# NES_IO.net
KiCad netlist of a schematic drawn in EAGLE
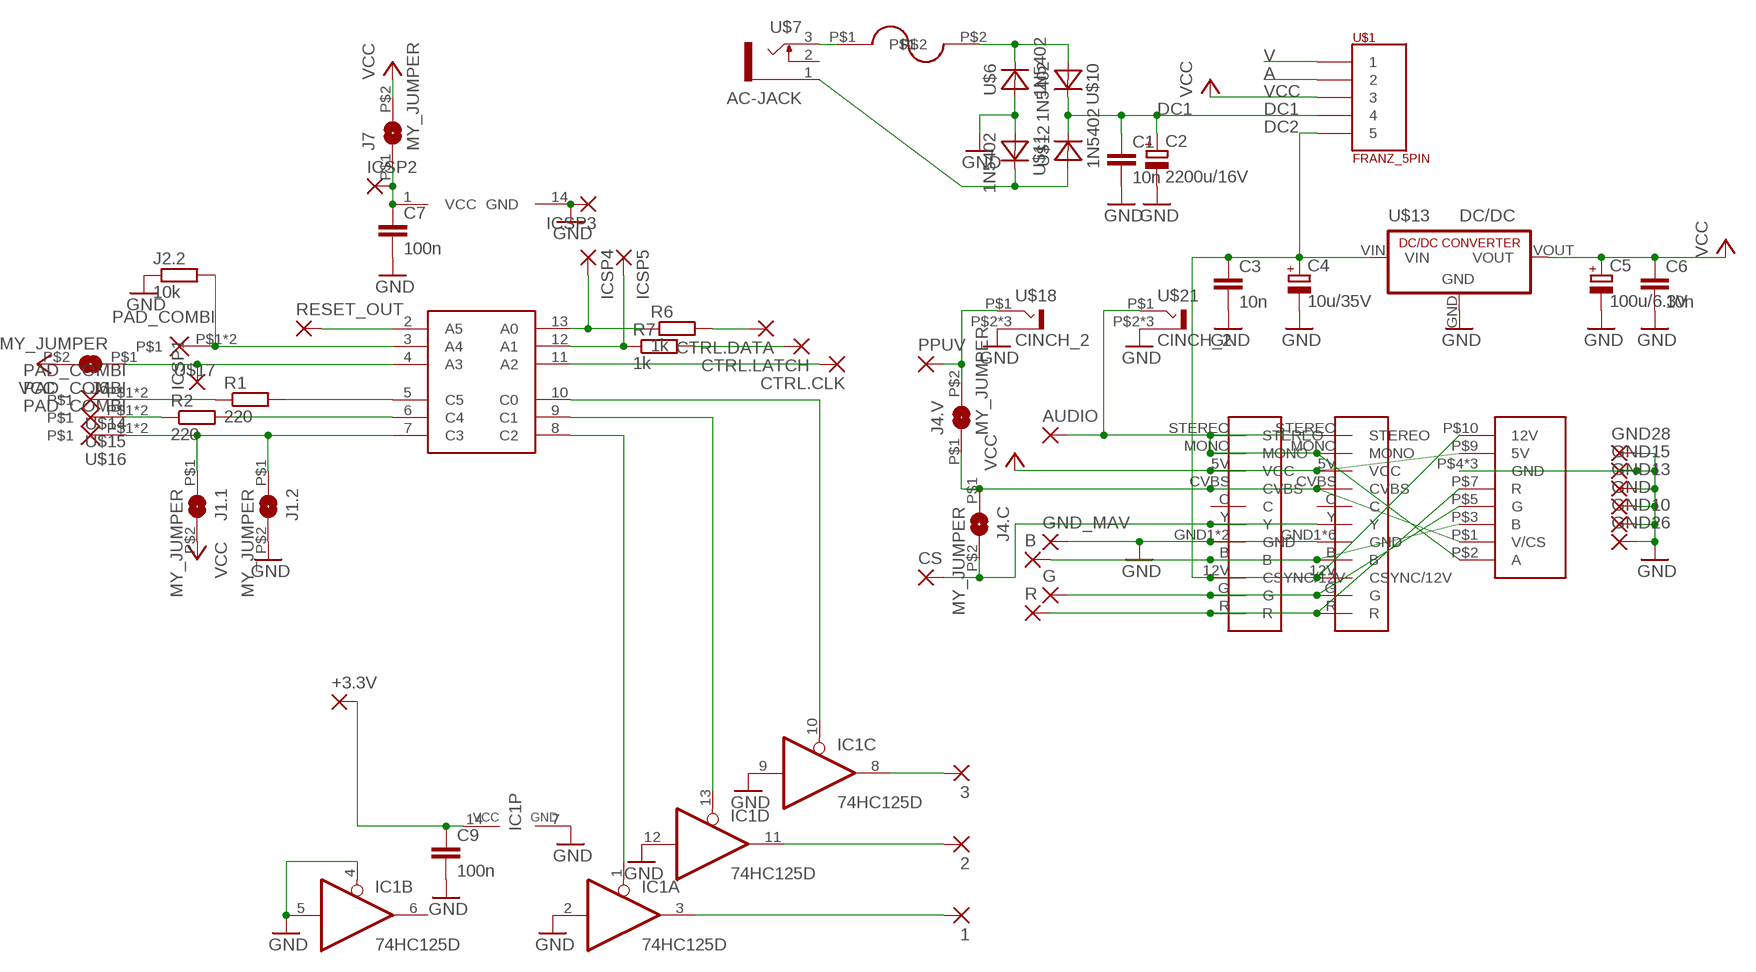
[diagram p0: schematic, sheet 1]

(export (version "E")
  (design (tool "Eeschema 10.0.6"))
  (components
    (comp (ref "+3.3V")
      (value "SMD2")
      (footprint "eagle-import:SMD1,27-2,54")
      (libsource (lib "eagle-import") (part "SMD2"))
    )
    (comp (ref "1")
      (value "SMD2")
      (footprint "eagle-import:SMD1,27-2,54")
      (libsource (lib "eagle-import") (part "SMD2"))
    )
    (comp (ref "2")
      (value "SMD2")
      (footprint "eagle-import:SMD1,27-2,54")
      (libsource (lib "eagle-import") (part "SMD2"))
    )
    (comp (ref "3")
      (value "SMD2")
      (footprint "eagle-import:SMD1,27-2,54")
      (libsource (lib "eagle-import") (part "SMD2"))
    )
    (comp (ref "AUDIO")
      (value "SMD2")
      (footprint "eagle-import:SMD1,27-2,54")
      (libsource (lib "eagle-import") (part "SMD2"))
    )
    (comp (ref "B")
      (value "SMD2")
      (footprint "eagle-import:SMD1,27-2,54")
      (libsource (lib "eagle-import") (part "SMD2"))
    )
    (comp (ref "C1")
      (value "10n")
      (footprint "eagle-import:Z0805")
      (libsource (lib "eagle-import") (part "C0805"))
    )
    (comp (ref "C2")
      (value "2200u/16V")
      (footprint "eagle-import:E5-13")
      (libsource (lib "eagle-import") (part "resistor_CPOL-EUE5-13"))
    )
    (comp (ref "C3")
      (value "10n")
      (footprint "eagle-import:Z0805")
      (libsource (lib "eagle-import") (part "C0805"))
    )
    (comp (ref "C4")
      (value "10u/35V")
      (footprint "eagle-import:PANASONIC_B")
      (libsource (lib "eagle-import") (part "CPOL-EUB"))
    )
    (comp (ref "C5")
      (value "100u/6.3V")
      (footprint "eagle-import:PANASONIC_D")
      (libsource (lib "eagle-import") (part "CPOL-EUD"))
    )
    (comp (ref "C6")
      (value "10n")
      (footprint "eagle-import:Z0805")
      (libsource (lib "eagle-import") (part "C0805"))
    )
    (comp (ref "C7")
      (value "100n")
      (footprint "eagle-import:Z0805")
      (libsource (lib "eagle-import") (part "C0805"))
    )
    (comp (ref "C9")
      (value "100n")
      (footprint "eagle-import:Z0805")
      (libsource (lib "eagle-import") (part "C0805"))
    )
    (comp (ref "CS")
      (value "SMD2")
      (footprint "eagle-import:SMD1,27-2,54")
      (libsource (lib "eagle-import") (part "SMD2"))
    )
    (comp (ref "CTRL.CLK")
      (value "SMD2")
      (footprint "eagle-import:SMD1,27-2,54")
      (libsource (lib "eagle-import") (part "SMD2"))
    )
    (comp (ref "CTRL.DATA")
      (value "SMD2")
      (footprint "eagle-import:SMD1,27-2,54")
      (libsource (lib "eagle-import") (part "SMD2"))
    )
    (comp (ref "CTRL.LATCH")
      (value "SMD2")
      (footprint "eagle-import:SMD1,27-2,54")
      (libsource (lib "eagle-import") (part "SMD2"))
    )
    (comp (ref "G")
      (value "SMD2")
      (footprint "eagle-import:SMD1,27-2,54")
      (libsource (lib "eagle-import") (part "SMD2"))
    )
    (comp (ref "GND")
      (value "SMD5")
      (footprint "eagle-import:SMD2,54-5,08")
      (libsource (lib "eagle-import") (part "SMD5"))
    )
    (comp (ref "GND10")
      (value "SMD5")
      (footprint "eagle-import:SMD2,54-5,08")
      (libsource (lib "eagle-import") (part "SMD5"))
    )
    (comp (ref "GND13")
      (value "SMD5")
      (footprint "eagle-import:SMD2,54-5,08")
      (libsource (lib "eagle-import") (part "SMD5"))
    )
    (comp (ref "GND15")
      (value "SMD5")
      (footprint "eagle-import:SMD2,54-5,08")
      (libsource (lib "eagle-import") (part "SMD5"))
    )
    (comp (ref "GND26")
      (value "SMD5")
      (footprint "eagle-import:SMD2,54-5,08")
      (libsource (lib "eagle-import") (part "SMD5"))
    )
    (comp (ref "GND28")
      (value "SMD5")
      (footprint "eagle-import:SMD2,54-5,08")
      (libsource (lib "eagle-import") (part "SMD5"))
    )
    (comp (ref "GND_MAV")
      (value "SMD2")
      (footprint "eagle-import:SMD1,27-2,54")
      (libsource (lib "eagle-import") (part "SMD2"))
    )
    (comp (ref "IC1")
      (value "74HC125D")
      (footprint "eagle-import:SO14")
      (libsource (lib "eagle-import") (part "74125DHC"))
    )
    (comp (ref "ICSP1")
      (value "1,6/0,8")
      (footprint "eagle-import:1,6_0,8")
      (libsource (lib "eagle-import") (part "1,6/0,8"))
    )
    (comp (ref "ICSP2")
      (value "1,6/0,8")
      (footprint "eagle-import:1,6_0,8")
      (libsource (lib "eagle-import") (part "1,6/0,8"))
    )
    (comp (ref "ICSP3")
      (value "1,6/0,8")
      (footprint "eagle-import:1,6_0,8")
      (libsource (lib "eagle-import") (part "1,6/0,8"))
    )
    (comp (ref "ICSP4")
      (value "1,6/0,8")
      (footprint "eagle-import:1,6_0,8")
      (libsource (lib "eagle-import") (part "1,6/0,8"))
    )
    (comp (ref "ICSP5")
      (value "1,6/0,8")
      (footprint "eagle-import:1,6_0,8")
      (libsource (lib "eagle-import") (part "1,6/0,8"))
    )
    (comp (ref "J1.1")
      (value "MY_JUMPER")
      (footprint "eagle-import:MYJUMP")
      (libsource (lib "eagle-import") (part "MY_JUMPER"))
    )
    (comp (ref "J1.2")
      (value "MY_JUMPER")
      (footprint "eagle-import:MYJUMP")
      (libsource (lib "eagle-import") (part "MY_JUMPER"))
    )
    (comp (ref "J2.2")
      (value "10k")
      (footprint "eagle-import:Z0805")
      (libsource (lib "eagle-import") (part "R0805"))
    )
    (comp (ref "J4.C")
      (value "MY_JUMPER")
      (footprint "eagle-import:MYJUMP")
      (libsource (lib "eagle-import") (part "MY_JUMPER"))
    )
    (comp (ref "J4.V")
      (value "MY_JUMPER")
      (footprint "eagle-import:MYJUMP")
      (libsource (lib "eagle-import") (part "MY_JUMPER"))
    )
    (comp (ref "J6")
      (value "MY_JUMPER")
      (footprint "eagle-import:MYJUMP")
      (libsource (lib "eagle-import") (part "MY_JUMPER"))
    )
    (comp (ref "J7")
      (value "MY_JUMPER")
      (footprint "eagle-import:MYJUMP")
      (libsource (lib "eagle-import") (part "MY_JUMPER"))
    )
    (comp (ref "PPUV")
      (value "SMD2")
      (footprint "eagle-import:SMD1,27-2,54")
      (libsource (lib "eagle-import") (part "SMD2"))
    )
    (comp (ref "R")
      (value "SMD2")
      (footprint "eagle-import:SMD1,27-2,54")
      (libsource (lib "eagle-import") (part "SMD2"))
    )
    (comp (ref "R1")
      (value "220")
      (footprint "eagle-import:Z0805")
      (libsource (lib "eagle-import") (part "R0805"))
    )
    (comp (ref "R2")
      (value "220")
      (footprint "eagle-import:Z0805")
      (libsource (lib "eagle-import") (part "R0805"))
    )
    (comp (ref "R6")
      (value "1k")
      (footprint "eagle-import:Z0805")
      (libsource (lib "eagle-import") (part "R0805"))
    )
    (comp (ref "R7")
      (value "1k")
      (footprint "eagle-import:Z0805")
      (libsource (lib "eagle-import") (part "R0805"))
    )
    (comp (ref "RESET_OUT")
      (value "SMD2")
      (footprint "eagle-import:SMD1,27-2,54")
      (libsource (lib "eagle-import") (part "SMD2"))
    )
    (comp (ref "U$1")
      (value "FRANZ_5PIN")
      (footprint "eagle-import:5X2.22RM4")
      (libsource (lib "eagle-import") (part "FRANZ_5PIN"))
    )
    (comp (ref "U$2")
      (value "FUSEHOLDER")
      (footprint "eagle-import:FUSEHOLDER")
      (libsource (lib "eagle-import") (part "FUSEHOLDER"))
    )
    (comp (ref "U$5")
      (value "PIC16F630_SIMPLE")
      (footprint "eagle-import:PIC16F630")
      (libsource (lib "eagle-import") (part "PIC16F630_SIMPLE"))
    )
    (comp (ref "U$6")
      (value "1N5402")
      (footprint "eagle-import:DO201")
      (libsource (lib "eagle-import") (part "1N5402"))
    )
    (comp (ref "U$7")
      (value "AC-JACK")
      (footprint "eagle-import:AC-JACK")
      (libsource (lib "eagle-import") (part "AC-JACK"))
    )
    (comp (ref "U$8")
      (value "NESFR_JACK2")
      (footprint "eagle-import:NESFR_JACK2")
      (libsource (lib "eagle-import") (part "NESFR_JACK2"))
    )
    (comp (ref "U$10")
      (value "1N5402")
      (footprint "eagle-import:DO201")
      (libsource (lib "eagle-import") (part "1N5402"))
    )
    (comp (ref "U$11")
      (value "1N5402")
      (footprint "eagle-import:DO201")
      (libsource (lib "eagle-import") (part "1N5402"))
    )
    (comp (ref "U$12")
      (value "1N5402")
      (footprint "eagle-import:DO201")
      (libsource (lib "eagle-import") (part "1N5402"))
    )
    (comp (ref "U$13")
      (value "DC/DC")
      (footprint "eagle-import:RECOM")
      (libsource (lib "eagle-import") (part "DC/DC"))
    )
    (comp (ref "U$14")
      (value "PAD_COMBI")
      (footprint "eagle-import:PAD_COMBI")
      (libsource (lib "eagle-import") (part "PAD_COMBI"))
    )
    (comp (ref "U$15")
      (value "PAD_COMBI")
      (footprint "eagle-import:PAD_COMBI")
      (libsource (lib "eagle-import") (part "PAD_COMBI"))
    )
    (comp (ref "U$16")
      (value "PAD_COMBI")
      (footprint "eagle-import:PAD_COMBI")
      (libsource (lib "eagle-import") (part "PAD_COMBI"))
    )
    (comp (ref "U$17")
      (value "PAD_COMBI")
      (footprint "eagle-import:PAD_COMBI")
      (libsource (lib "eagle-import") (part "PAD_COMBI"))
    )
    (comp (ref "U$18")
      (value "CINCH_2")
      (footprint "eagle-import:CINCH_2")
      (libsource (lib "eagle-import") (part "CINCH_2"))
    )
    (comp (ref "U$19")
      (value "GC-MULTIAV")
      (footprint "eagle-import:GC-MULTIAV")
      (libsource (lib "eagle-import") (part "GC-MULTIAV"))
    )
    (comp (ref "U$20")
      (value "SNES-MULTIAV2")
      (footprint "eagle-import:SNES-MULTIAV2")
      (libsource (lib "eagle-import") (part "SNES-MULTIAV2"))
    )
    (comp (ref "U$21")
      (value "CINCH_2")
      (footprint "eagle-import:CINCH_2")
      (libsource (lib "eagle-import") (part "CINCH_2"))
    )
  )
  (nets
    (net (code "1") (name "/A") (class "Default")
      (node (ref "U$1") (pin "P$2") (pinfunction "2_P$2") (pintype "bidirectional"))
    )
    (net (code "2") (name "/DC1") (class "Default")
      (node (ref "C1") (pin "1") (pinfunction "1_1") (pintype "passive"))
      (node (ref "C2") (pin "+") (pinfunction "+_+") (pintype "passive"))
      (node (ref "U$1") (pin "P$4") (pinfunction "4_P$4") (pintype "bidirectional"))
      (node (ref "U$10") (pin "C") (pinfunction "C_C") (pintype "passive"))
      (node (ref "U$12") (pin "C") (pinfunction "C_C") (pintype "passive"))
    )
    (net (code "3") (name "/DC2") (class "Default")
      (node (ref "C3") (pin "1") (pinfunction "1_1") (pintype "passive"))
      (node (ref "C4") (pin "+") (pinfunction "+_+") (pintype "passive"))
      (node (ref "U$1") (pin "P$5") (pinfunction "5_P$5") (pintype "bidirectional"))
      (node (ref "U$13") (pin "VIN") (pinfunction "VIN_VIN") (pintype "passive"))
      (node (ref "U$19") (pin "12V") (pinfunction "CSYNC/12V_12V") (pintype "output"))
      (node (ref "U$20") (pin "12V") (pinfunction "CSYNC/12V_12V") (pintype "output"))
      (node (ref "U$8") (pin "P$10") (pinfunction "12V_P$10") (pintype "bidirectional"))
    )
    (net (code "4") (name "/V") (class "Default")
      (node (ref "U$1") (pin "P$1") (pinfunction "1_P$1") (pintype "bidirectional"))
    )
    (net (code "5") (name "GND") (class "Default")
      (node (ref "C1") (pin "2") (pinfunction "2_2") (pintype "passive"))
      (node (ref "C2") (pin "-") (pinfunction "-_-") (pintype "passive"))
      (node (ref "C3") (pin "2") (pinfunction "2_2") (pintype "passive"))
      (node (ref "C4") (pin "-") (pinfunction "-_-") (pintype "passive"))
      (node (ref "C5") (pin "-") (pinfunction "-_-") (pintype "passive"))
      (node (ref "C6") (pin "2") (pinfunction "2_2") (pintype "passive"))
      (node (ref "C7") (pin "2") (pinfunction "2_2") (pintype "passive"))
      (node (ref "C9") (pin "2") (pinfunction "2_2") (pintype "passive"))
      (node (ref "GND") (pin "1") (pinfunction "P_1") (pintype "passive"))
      (node (ref "GND10") (pin "1") (pinfunction "P_1") (pintype "passive"))
      (node (ref "GND13") (pin "1") (pinfunction "P_1") (pintype "passive"))
      (node (ref "GND15") (pin "1") (pinfunction "P_1") (pintype "passive"))
      (node (ref "GND26") (pin "1") (pinfunction "P_1") (pintype "passive"))
      (node (ref "GND28") (pin "1") (pinfunction "P_1") (pintype "passive"))
      (node (ref "GND_MAV") (pin "1") (pinfunction "P_1") (pintype "passive"))
      (node (ref "IC1") (pin "12") (pinfunction "I_12") (pintype "input"))
      (node (ref "IC1") (pin "2") (pinfunction "I_2") (pintype "input"))
      (node (ref "IC1") (pin "4") (pinfunction "OE_4") (pintype "input"))
      (node (ref "IC1") (pin "5") (pinfunction "I_5") (pintype "input"))
      (node (ref "IC1") (pin "7") (pinfunction "GND_7") (pintype "power_in"))
      (node (ref "IC1") (pin "9") (pinfunction "I_9") (pintype "input"))
      (node (ref "ICSP3") (pin "1") (pinfunction "P_1") (pintype "passive"))
      (node (ref "J1.2") (pin "P$2") (pinfunction "2_P$2") (pintype "passive"))
      (node (ref "J2.2") (pin "1") (pinfunction "1_1") (pintype "passive"))
      (node (ref "U$11") (pin "A") (pinfunction "A_A") (pintype "passive"))
      (node (ref "U$13") (pin "GND") (pinfunction "GND_GND") (pintype "passive"))
      (node (ref "U$18") (pin "P$2") (pinfunction "S_P$2") (pintype "passive"))
      (node (ref "U$18") (pin "P$3") (pinfunction "S_P$3") (pintype "passive"))
      (node (ref "U$18") (pin "P$4") (pinfunction "S_P$4") (pintype "passive"))
      (node (ref "U$19") (pin "GND1") (pinfunction "GND_GND1") (pintype "output"))
      (node (ref "U$19") (pin "GND2") (pinfunction "GND_GND2") (pintype "output"))
      (node (ref "U$19") (pin "GND3") (pinfunction "GND_GND3") (pintype "output"))
      (node (ref "U$19") (pin "GND4") (pinfunction "GND_GND4") (pintype "output"))
      (node (ref "U$19") (pin "GND5") (pinfunction "GND_GND5") (pintype "output"))
      (node (ref "U$19") (pin "GND6") (pinfunction "GND_GND6") (pintype "output"))
      (node (ref "U$20") (pin "GND1") (pinfunction "GND_GND1") (pintype "output"))
      (node (ref "U$20") (pin "GND2") (pinfunction "GND_GND2") (pintype "output"))
      (node (ref "U$21") (pin "P$2") (pinfunction "S_P$2") (pintype "passive"))
      (node (ref "U$21") (pin "P$3") (pinfunction "S_P$3") (pintype "passive"))
      (node (ref "U$21") (pin "P$4") (pinfunction "S_P$4") (pintype "passive"))
      (node (ref "U$5") (pin "14") (pinfunction "GND_14") (pintype "bidirectional"))
      (node (ref "U$6") (pin "A") (pinfunction "A_A") (pintype "passive"))
      (node (ref "U$8") (pin "P$4") (pinfunction "GND_P$4") (pintype "bidirectional"))
      (node (ref "U$8") (pin "P$6") (pinfunction "GND_P$6") (pintype "bidirectional"))
      (node (ref "U$8") (pin "P$8") (pinfunction "GND_P$8") (pintype "bidirectional"))
    )
    (net (code "6") (name "Net-(+3.3V-P)") (class "Default")
      (node (ref "+3.3V") (pin "1") (pinfunction "P_1") (pintype "passive"))
      (node (ref "C9") (pin "1") (pinfunction "1_1") (pintype "passive"))
      (node (ref "IC1") (pin "14") (pinfunction "VCC_14") (pintype "power_in"))
    )
    (net (code "7") (name "Net-(1-P)") (class "Default")
      (node (ref "1") (pin "1") (pinfunction "P_1") (pintype "passive"))
      (node (ref "IC1") (pin "3") (pinfunction "O_3") (pintype "tri_state"))
    )
    (net (code "8") (name "Net-(2-P)") (class "Default")
      (node (ref "2") (pin "1") (pinfunction "P_1") (pintype "passive"))
      (node (ref "IC1") (pin "11") (pinfunction "O_11") (pintype "tri_state"))
    )
    (net (code "9") (name "Net-(3-P)") (class "Default")
      (node (ref "3") (pin "1") (pinfunction "P_1") (pintype "passive"))
      (node (ref "IC1") (pin "8") (pinfunction "O_8") (pintype "tri_state"))
    )
    (net (code "10") (name "Net-(AUDIO-P)") (class "Default")
      (node (ref "AUDIO") (pin "1") (pinfunction "P_1") (pintype "passive"))
      (node (ref "U$19") (pin "MONO") (pinfunction "MONO_MONO") (pintype "output"))
      (node (ref "U$19") (pin "STEREO") (pinfunction "STEREO_STEREO") (pintype "output"))
      (node (ref "U$20") (pin "MONO") (pinfunction "MONO_MONO") (pintype "output"))
      (node (ref "U$20") (pin "STEREO") (pinfunction "STEREO_STEREO") (pintype "output"))
      (node (ref "U$21") (pin "P$1") (pinfunction "T_P$1") (pintype "passive"))
      (node (ref "U$8") (pin "P$2") (pinfunction "A_P$2") (pintype "bidirectional"))
    )
    (net (code "11") (name "Net-(B-P)") (class "Default")
      (node (ref "B") (pin "1") (pinfunction "P_1") (pintype "passive"))
      (node (ref "U$19") (pin "B") (pinfunction "B_B") (pintype "output"))
      (node (ref "U$20") (pin "B") (pinfunction "B_B") (pintype "output"))
      (node (ref "U$8") (pin "P$3") (pinfunction "B_P$3") (pintype "bidirectional"))
    )
    (net (code "12") (name "Net-(CS-P)") (class "Default")
      (node (ref "CS") (pin "1") (pinfunction "P_1") (pintype "passive"))
      (node (ref "J4.C") (pin "P$2") (pinfunction "2_P$2") (pintype "passive"))
      (node (ref "U$19") (pin "Y") (pinfunction "Y_Y") (pintype "output"))
      (node (ref "U$20") (pin "Y") (pinfunction "Y_Y") (pintype "output"))
    )
    (net (code "13") (name "Net-(CTRL.CLK-P)") (class "Default")
      (node (ref "CTRL.CLK") (pin "1") (pinfunction "P_1") (pintype "passive"))
      (node (ref "U$5") (pin "11") (pinfunction "A2_11") (pintype "bidirectional"))
    )
    (net (code "14") (name "Net-(CTRL.DATA-P)") (class "Default")
      (node (ref "CTRL.DATA") (pin "1") (pinfunction "P_1") (pintype "passive"))
      (node (ref "R6") (pin "2") (pinfunction "2_2") (pintype "passive"))
    )
    (net (code "15") (name "Net-(CTRL.LATCH-P)") (class "Default")
      (node (ref "CTRL.LATCH") (pin "1") (pinfunction "P_1") (pintype "passive"))
      (node (ref "R7") (pin "2") (pinfunction "2_2") (pintype "passive"))
    )
    (net (code "16") (name "Net-(G-P)") (class "Default")
      (node (ref "G") (pin "1") (pinfunction "P_1") (pintype "passive"))
      (node (ref "U$19") (pin "G") (pinfunction "G_G") (pintype "output"))
      (node (ref "U$20") (pin "G") (pinfunction "G_G") (pintype "output"))
      (node (ref "U$8") (pin "P$5") (pinfunction "G_P$5") (pintype "bidirectional"))
    )
    (net (code "17") (name "Net-(IC1A-OE)") (class "Default")
      (node (ref "IC1") (pin "1") (pinfunction "OE_1") (pintype "input"))
      (node (ref "U$5") (pin "8") (pinfunction "C2_8") (pintype "bidirectional"))
    )
    (net (code "18") (name "Net-(IC1C-OE)") (class "Default")
      (node (ref "IC1") (pin "10") (pinfunction "OE_10") (pintype "input"))
      (node (ref "U$5") (pin "10") (pinfunction "C0_10") (pintype "bidirectional"))
    )
    (net (code "19") (name "Net-(IC1D-OE)") (class "Default")
      (node (ref "IC1") (pin "13") (pinfunction "OE_13") (pintype "input"))
      (node (ref "U$5") (pin "9") (pinfunction "C1_9") (pintype "bidirectional"))
    )
    (net (code "20") (name "Net-(ICSP1-P)") (class "Default")
      (node (ref "ICSP1") (pin "1") (pinfunction "P_1") (pintype "passive"))
      (node (ref "J6") (pin "P$1") (pinfunction "1_P$1") (pintype "passive"))
      (node (ref "U$5") (pin "4") (pinfunction "A3_4") (pintype "bidirectional"))
    )
    (net (code "21") (name "Net-(ICSP2-P)") (class "Default")
      (node (ref "C7") (pin "1") (pinfunction "1_1") (pintype "passive"))
      (node (ref "ICSP2") (pin "1") (pinfunction "P_1") (pintype "passive"))
      (node (ref "J7") (pin "P$1") (pinfunction "1_P$1") (pintype "passive"))
      (node (ref "U$5") (pin "1") (pinfunction "VCC_1") (pintype "bidirectional"))
    )
    (net (code "22") (name "Net-(ICSP4-P)") (class "Default")
      (node (ref "ICSP4") (pin "1") (pinfunction "P_1") (pintype "passive"))
      (node (ref "R6") (pin "1") (pinfunction "1_1") (pintype "passive"))
      (node (ref "U$5") (pin "13") (pinfunction "A0_13") (pintype "bidirectional"))
    )
    (net (code "23") (name "Net-(ICSP5-P)") (class "Default")
      (node (ref "ICSP5") (pin "1") (pinfunction "P_1") (pintype "passive"))
      (node (ref "R7") (pin "1") (pinfunction "1_1") (pintype "passive"))
      (node (ref "U$5") (pin "12") (pinfunction "A1_12") (pintype "bidirectional"))
    )
    (net (code "24") (name "Net-(J1.1-1)") (class "Default")
      (node (ref "J1.1") (pin "P$1") (pinfunction "1_P$1") (pintype "passive"))
      (node (ref "J1.2") (pin "P$1") (pinfunction "1_P$1") (pintype "passive"))
      (node (ref "U$16") (pin "P$1") (pinfunction "P$1_P$1") (pintype "bidirectional"))
      (node (ref "U$16") (pin "P$2") (pinfunction "P$1_P$2") (pintype "bidirectional"))
      (node (ref "U$5") (pin "7") (pinfunction "C3_7") (pintype "bidirectional"))
    )
    (net (code "25") (name "Net-(J4.C-1)") (class "Default")
      (node (ref "J4.C") (pin "P$1") (pinfunction "1_P$1") (pintype "passive"))
      (node (ref "J4.V") (pin "P$1") (pinfunction "1_P$1") (pintype "passive"))
      (node (ref "U$19") (pin "CVBS") (pinfunction "CVBS_CVBS") (pintype "output"))
      (node (ref "U$20") (pin "CVBS") (pinfunction "CVBS_CVBS") (pintype "output"))
      (node (ref "U$8") (pin "P$1") (pinfunction "V/CS_P$1") (pintype "bidirectional"))
    )
    (net (code "26") (name "Net-(J4.V-2)") (class "Default")
      (node (ref "J4.V") (pin "P$2") (pinfunction "2_P$2") (pintype "passive"))
      (node (ref "PPUV") (pin "1") (pinfunction "P_1") (pintype "passive"))
      (node (ref "U$18") (pin "P$1") (pinfunction "T_P$1") (pintype "passive"))
    )
    (net (code "27") (name "Net-(R-P)") (class "Default")
      (node (ref "R") (pin "1") (pinfunction "P_1") (pintype "passive"))
      (node (ref "U$19") (pin "R") (pinfunction "R_R") (pintype "output"))
      (node (ref "U$20") (pin "R") (pinfunction "R_R") (pintype "output"))
      (node (ref "U$8") (pin "P$7") (pinfunction "R_P$7") (pintype "bidirectional"))
    )
    (net (code "28") (name "Net-(R1-Pad1)") (class "Default")
      (node (ref "R1") (pin "1") (pinfunction "1_1") (pintype "passive"))
      (node (ref "U$14") (pin "P$1") (pinfunction "P$1_P$1") (pintype "bidirectional"))
      (node (ref "U$14") (pin "P$2") (pinfunction "P$1_P$2") (pintype "bidirectional"))
    )
    (net (code "29") (name "Net-(R2-Pad1)") (class "Default")
      (node (ref "R2") (pin "1") (pinfunction "1_1") (pintype "passive"))
      (node (ref "U$15") (pin "P$1") (pinfunction "P$1_P$1") (pintype "bidirectional"))
      (node (ref "U$15") (pin "P$2") (pinfunction "P$1_P$2") (pintype "bidirectional"))
    )
    (net (code "30") (name "Net-(RESET_OUT-P)") (class "Default")
      (node (ref "RESET_OUT") (pin "1") (pinfunction "P_1") (pintype "passive"))
      (node (ref "U$5") (pin "2") (pinfunction "A5_2") (pintype "bidirectional"))
    )
    (net (code "31") (name "Net-(U$2-PadP$1)") (class "Default")
      (node (ref "U$2") (pin "P$1") (pinfunction "P$1_P$1") (pintype "bidirectional"))
      (node (ref "U$7") (pin "3") (pinfunction "3_3") (pintype "passive"))
    )
    (net (code "32") (name "Net-(U$5A-A4)") (class "Default")
      (node (ref "J2.2") (pin "2") (pinfunction "2_2") (pintype "passive"))
      (node (ref "U$17") (pin "P$1") (pinfunction "P$1_P$1") (pintype "bidirectional"))
      (node (ref "U$17") (pin "P$2") (pinfunction "P$1_P$2") (pintype "bidirectional"))
      (node (ref "U$5") (pin "3") (pinfunction "A4_3") (pintype "bidirectional"))
    )
    (net (code "33") (name "Net-(U$5A-C4)") (class "Default")
      (node (ref "R2") (pin "2") (pinfunction "2_2") (pintype "passive"))
      (node (ref "U$5") (pin "6") (pinfunction "C4_6") (pintype "bidirectional"))
    )
    (net (code "34") (name "Net-(U$5A-C5)") (class "Default")
      (node (ref "R1") (pin "2") (pinfunction "2_2") (pintype "passive"))
      (node (ref "U$5") (pin "5") (pinfunction "C5_5") (pintype "bidirectional"))
    )
    (net (code "35") (name "Net-(U$7-5)") (class "Default")
      (node (ref "U$11") (pin "C") (pinfunction "C_C") (pintype "passive"))
      (node (ref "U$12") (pin "A") (pinfunction "A_A") (pintype "passive"))
      (node (ref "U$7") (pin "1") (pinfunction "5_1") (pintype "passive"))
    )
    (net (code "36") (name "Net-(U$10-PadA)") (class "Default")
      (node (ref "U$10") (pin "A") (pinfunction "A_A") (pintype "passive"))
      (node (ref "U$2") (pin "P$2") (pinfunction "P$2_P$2") (pintype "bidirectional"))
      (node (ref "U$6") (pin "C") (pinfunction "C_C") (pintype "passive"))
    )
    (net (code "37") (name "VCC") (class "Default")
      (node (ref "C5") (pin "+") (pinfunction "+_+") (pintype "passive"))
      (node (ref "C6") (pin "1") (pinfunction "1_1") (pintype "passive"))
      (node (ref "J1.1") (pin "P$2") (pinfunction "2_P$2") (pintype "passive"))
      (node (ref "J6") (pin "P$2") (pinfunction "2_P$2") (pintype "passive"))
      (node (ref "J7") (pin "P$2") (pinfunction "2_P$2") (pintype "passive"))
      (node (ref "U$1") (pin "P$3") (pinfunction "3_P$3") (pintype "bidirectional"))
      (node (ref "U$13") (pin "VOUT") (pinfunction "VOUT_VOUT") (pintype "passive"))
      (node (ref "U$19") (pin "5V") (pinfunction "VCC_5V") (pintype "output"))
      (node (ref "U$20") (pin "5V") (pinfunction "VCC_5V") (pintype "output"))
      (node (ref "U$8") (pin "P$9") (pinfunction "5V_P$9") (pintype "bidirectional"))
    )
    (net (code "38") (name "unconnected-(IC1B-O-Pad6)") (class "Default")
      (node (ref "IC1") (pin "6") (pinfunction "O_6") (pintype "tri_state"))
    )
    (net (code "39") (name "unconnected-(U$7-4-Pad2)") (class "Default")
      (node (ref "U$7") (pin "2") (pinfunction "4_2") (pintype "passive"))
    )
    (net (code "40") (name "unconnected-(U$19-PadC)") (class "Default")
      (node (ref "U$19") (pin "C") (pinfunction "C_C") (pintype "output"))
    )
    (net (code "41") (name "unconnected-(U$20-PadC)") (class "Default")
      (node (ref "U$20") (pin "C") (pinfunction "C_C") (pintype "output"))
    )
  )
)
